# Sheet1.net
KiCad netlist of a schematic drawn in Altium Designer
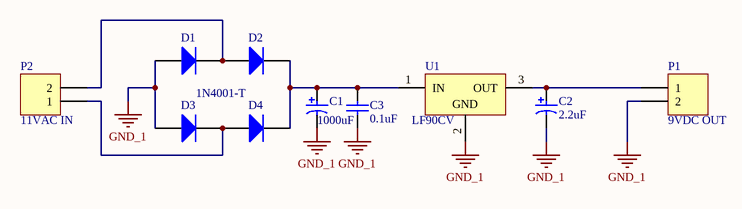
[diagram p0: Sheet1.SchDoc]

(export (version "E")
  (design (tool "Eeschema 10.0.6"))
  (components
    (comp (ref "C1")
      (value "1000uF")
      (footprint "PNSC-EEUFM1H221-2")
      (fields (field (name "MANUFACTURER") "Panasonic"))
      (libsource (lib "Altium Content Vault") (part "CAP-P-2"))
    )
    (comp (ref "C2")
      (value "2.2uF")
      (footprint "CAPPR55-200-1100X500X1200")
      (description "Aluminum Electrolytic Capacitor, 2.2 uF, +/- 20%, 50 V, -40 to 85 degC, 2-Pin THD, RoHS, Bulk")
      (libsource (lib "Altium Content Vault") (part "CAP-P-2"))
    )
    (comp (ref "C3")
      (value "0.1uF")
      (footprint "VISH-K104K15X7RF5TL2")
      (description "Ceramic Capacitor, 100 nF, +/- 10%, 50 V, -55 to 125 degC, 2-Pin THD, RoHS, Tape and Reel")
      (fields (field (name "MANUFACTURER") "Vishay") (field (name "TOLERANCE") "±10%"))
      (libsource (lib "Altium Content Vault") (part "CAP-NP-2"))
    )
    (comp (ref "D1")
      (value "1N4001-T")
      (footprint "DIOD-DO-41-P-2_V")
      (description "1.0 A Rectifier, 15 pF, 50 V, -65 to 150 degC, 2-Pin DO-41 Plastic, RoHS, Tape and Reel")
      (fields (field (name "MANUFACTURER") "Diodes Inc"))
      (libsource (lib "Altium Content Vault") (part "DIOD-D-A1K2-2"))
    )
    (comp (ref "D2")
      (value "1N4001-T")
      (footprint "DIOD-DO-41-P-2_V")
      (description "1.0 A Rectifier, 15 pF, 50 V, -65 to 150 degC, 2-Pin DO-41 Plastic, RoHS, Tape and Reel")
      (fields (field (name "MANUFACTURER") "Diodes Inc"))
      (libsource (lib "Altium Content Vault") (part "DIOD-D-A1K2-2"))
    )
    (comp (ref "D3")
      (value "1N4001-T")
      (footprint "DIOD-DO-41-P-2_V")
      (description "1.0 A Rectifier, 15 pF, 50 V, -65 to 150 degC, 2-Pin DO-41 Plastic, RoHS, Tape and Reel")
      (fields (field (name "MANUFACTURER") "Diodes Inc"))
      (libsource (lib "Altium Content Vault") (part "DIOD-D-A1K2-2"))
    )
    (comp (ref "D4")
      (value "1N4001-T")
      (footprint "DIOD-DO-41-P-2_V")
      (description "1.0 A Rectifier, 15 pF, 50 V, -65 to 150 degC, 2-Pin DO-41 Plastic, RoHS, Tape and Reel")
      (fields (field (name "MANUFACTURER") "Diodes Inc"))
      (libsource (lib "Altium Content Vault") (part "DIOD-D-A1K2-2"))
    )
    (comp (ref "P1")
      (value "9VDC OUT")
      (footprint "MHDR1X2")
      (description "Header, 2-Pin")
      (fields (field (name "PUBLISHER") "Altium Limited"))
      (libsource (lib "") (part "MHDR1X2_1"))
    )
    (comp (ref "P2")
      (value "11VAC IN")
      (footprint "MHDR1X2")
      (description "Header, 2-Pin")
      (fields (field (name "PUBLISHER") "Altium Limited"))
      (libsource (lib "Miscellaneous Connectors") (part "MHDR1X2"))
    )
    (comp (ref "U1")
      (value "LF90CV")
      (footprint "TO220")
      (description "500mA, Very Low Drop (0.45V) Voltage Regulator, 9V, 3-Pin TO-220")
      (libsource (lib "Altium Content Vault") (part "PM-REG-L4940-SIL3"))
    )
  )
  (nets
    (net (code "1") (name "GND_1") (class "Default")
      (node (ref "C1") (pin "2") (pinfunction "2_2") (pintype "passive"))
      (node (ref "C2") (pin "2") (pinfunction "2_2") (pintype "passive"))
      (node (ref "C3") (pin "1") (pinfunction "1_1") (pintype "passive"))
      (node (ref "D1") (pin "1") (pinfunction "A_1") (pintype "passive"))
      (node (ref "D3") (pin "1") (pinfunction "A_1") (pintype "passive"))
      (node (ref "P1") (pin "2") (pinfunction "2_2") (pintype "passive"))
      (node (ref "U1") (pin "2") (pinfunction "GND_2") (pintype "power_in"))
    )
    (net (code "2") (name "Net-(D1-K)") (class "Default")
      (node (ref "D1") (pin "2") (pinfunction "K_2") (pintype "passive"))
      (node (ref "D2") (pin "1") (pinfunction "A_1") (pintype "passive"))
      (node (ref "P2") (pin "2") (pinfunction "2_2") (pintype "passive"))
    )
    (net (code "3") (name "Net-(D2-K)") (class "Default")
      (node (ref "C1") (pin "1") (pinfunction "1_1") (pintype "passive"))
      (node (ref "C3") (pin "2") (pinfunction "2_2") (pintype "passive"))
      (node (ref "D2") (pin "2") (pinfunction "K_2") (pintype "passive"))
      (node (ref "D4") (pin "2") (pinfunction "K_2") (pintype "passive"))
      (node (ref "U1") (pin "1") (pinfunction "IN_1") (pintype "power_in"))
    )
    (net (code "4") (name "Net-(D3-K)") (class "Default")
      (node (ref "D3") (pin "2") (pinfunction "K_2") (pintype "passive"))
      (node (ref "D4") (pin "1") (pinfunction "A_1") (pintype "passive"))
      (node (ref "P2") (pin "1") (pinfunction "1_1") (pintype "passive"))
    )
    (net (code "5") (name "Net-(U1-OUT)") (class "Default")
      (node (ref "C2") (pin "1") (pinfunction "1_1") (pintype "passive"))
      (node (ref "P1") (pin "1") (pinfunction "1_1") (pintype "passive"))
      (node (ref "U1") (pin "3") (pinfunction "OUT_3") (pintype "power_in"))
    )
  )
)
